# SCH_New-Project-123_2026-03-22.net
KiCad netlist of a schematic drawn in EasyEDA
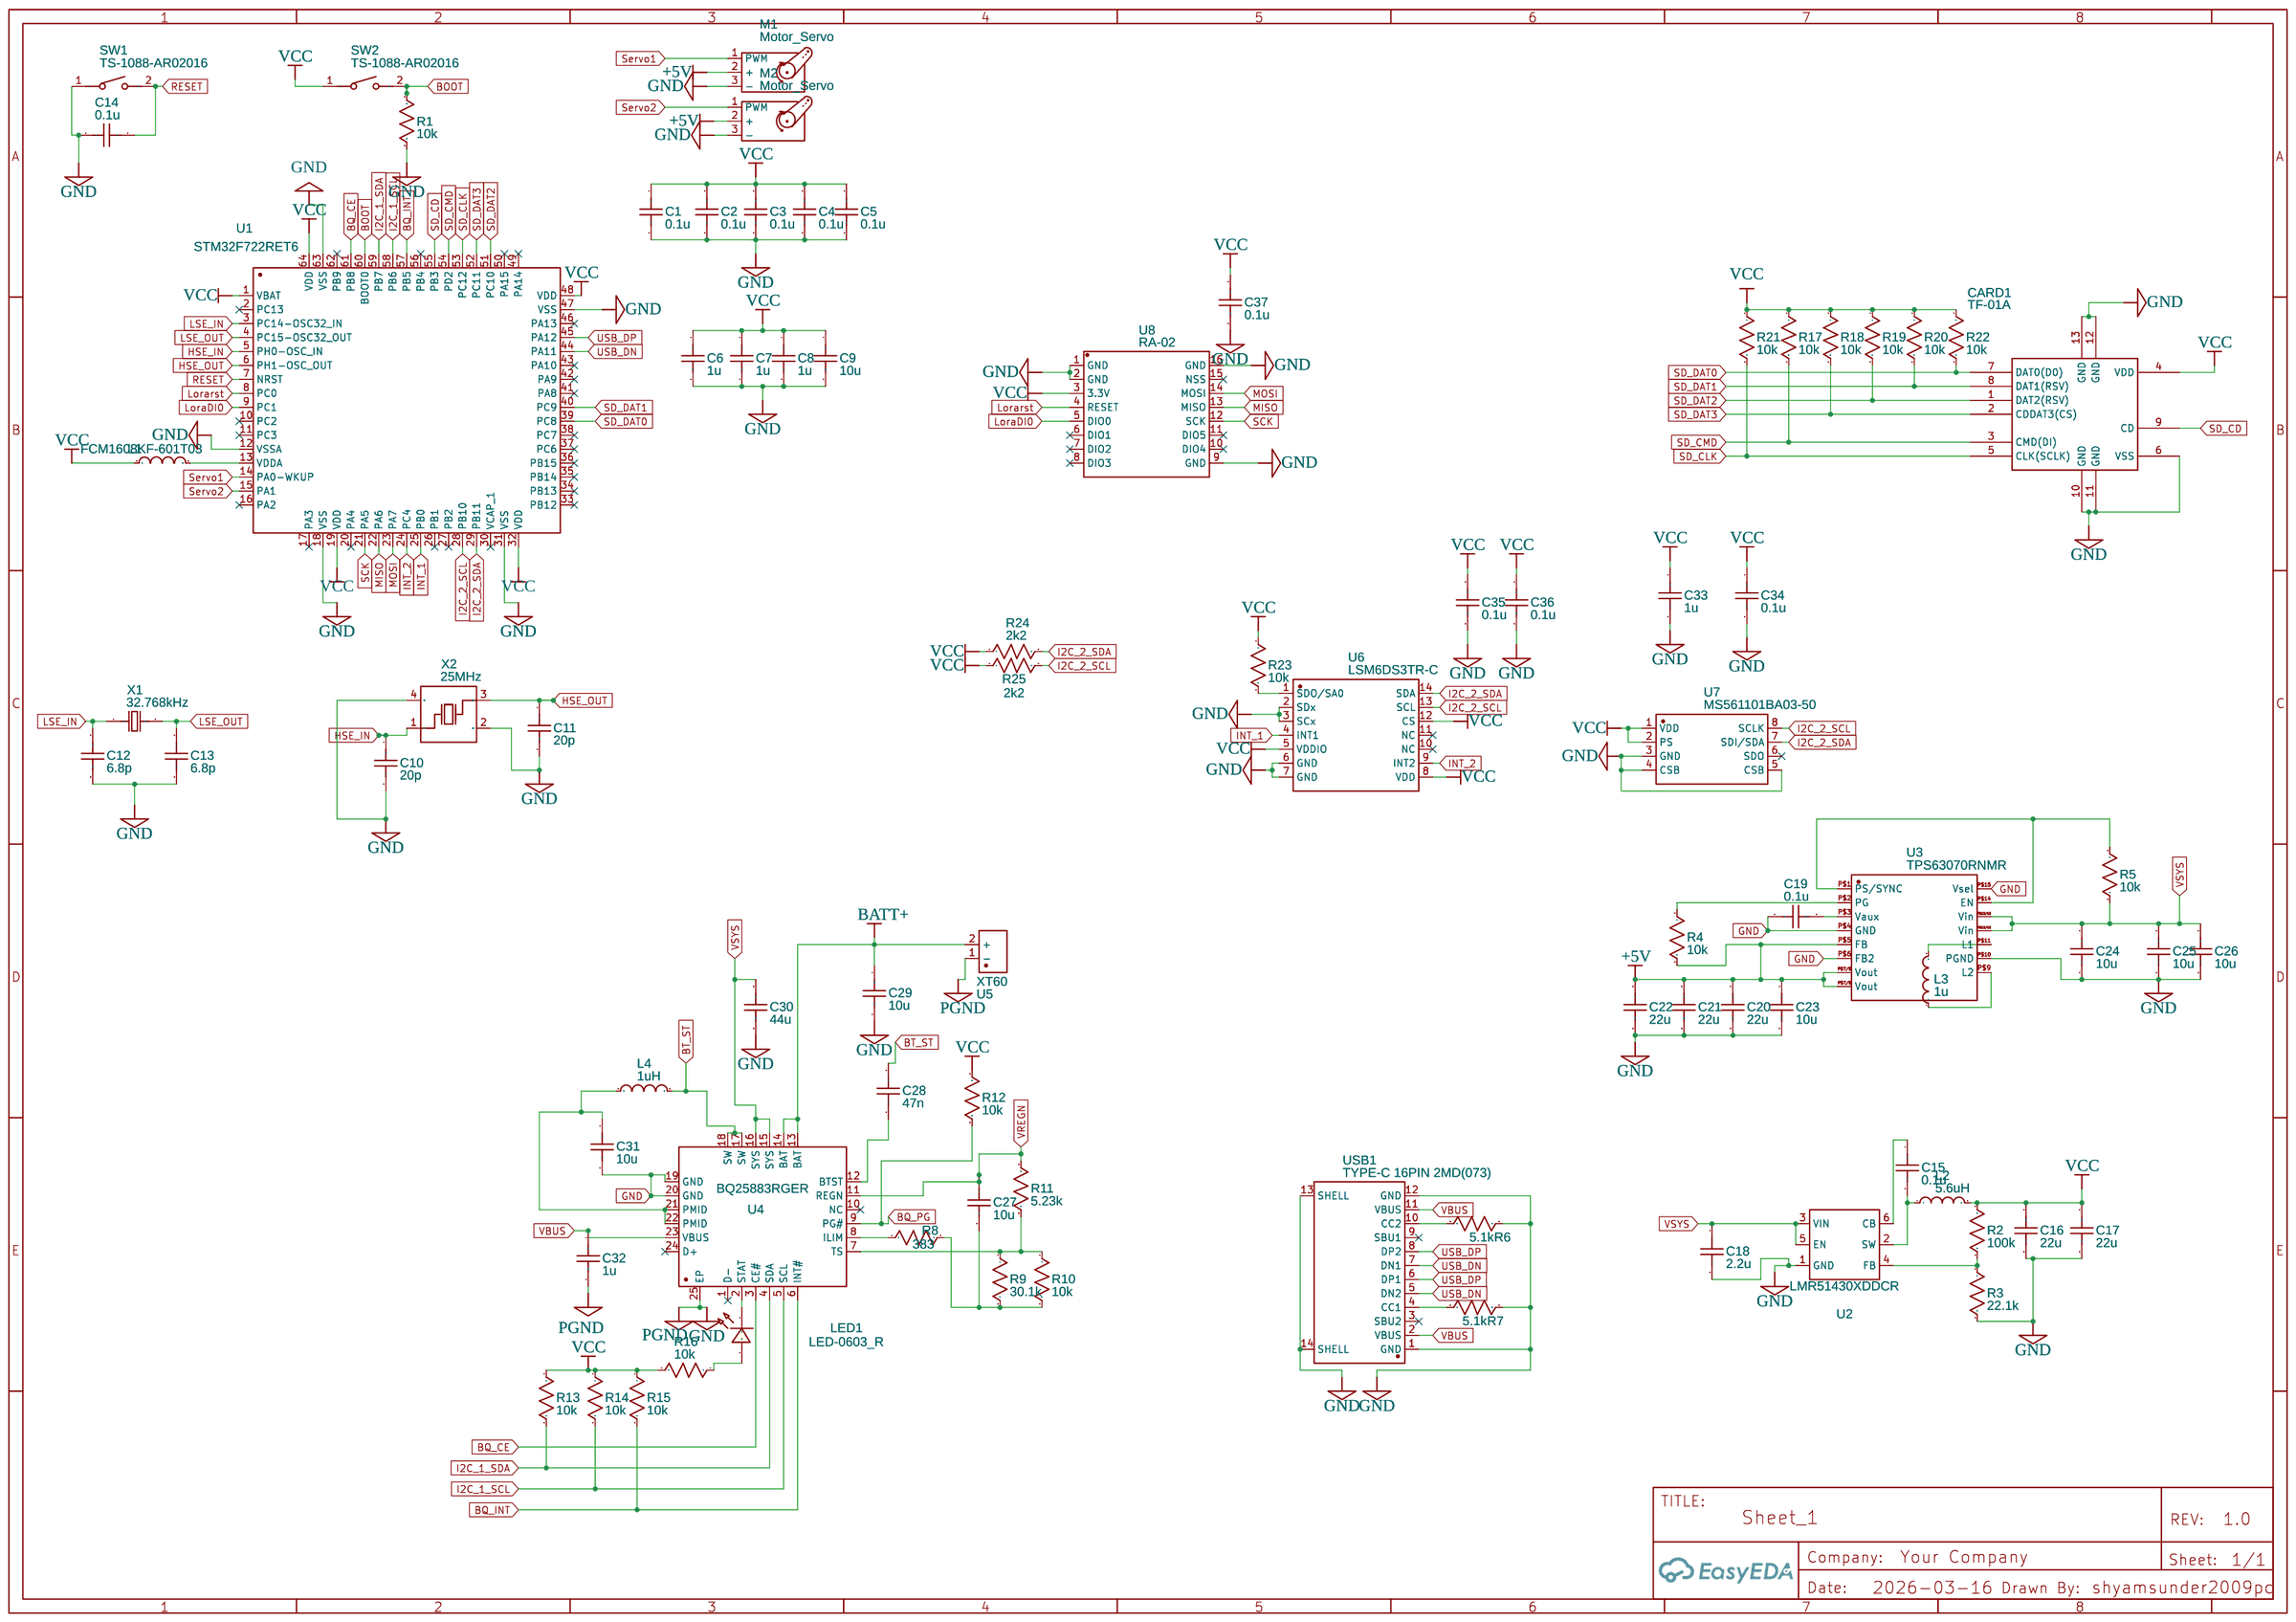
[diagram p0: schematic sheet]

(export (version "E")
  (design (tool "Eeschema 10.0.6"))
  (components
    (comp (ref "C1") (value "0.1u") (libsource (lib "") (part "C_0603_US")))
    (comp (ref "C2") (value "0.1u") (libsource (lib "") (part "C_0603_US")))
    (comp (ref "C3") (value "0.1u") (libsource (lib "") (part "C_0603_US")))
    (comp (ref "C4") (value "0.1u") (libsource (lib "") (part "C_0603_US")))
    (comp (ref "C5") (value "0.1u") (libsource (lib "") (part "C_0603_US")))
    (comp (ref "C6") (value "1u") (libsource (lib "") (part "C_0603_US")))
    (comp (ref "C7") (value "1u") (libsource (lib "") (part "C_0603_US")))
    (comp (ref "C8") (value "1u") (libsource (lib "") (part "C_0603_US")))
    (comp (ref "C9") (value "10u") (libsource (lib "") (part "C_0603_US")))
    (comp (ref "C10") (value "20p") (libsource (lib "") (part "C_0603_US")))
    (comp (ref "C11") (value "20p") (libsource (lib "") (part "C_0603_US")))
    (comp (ref "C12") (value "6.8p") (libsource (lib "") (part "C_0603_US")))
    (comp (ref "C13") (value "6.8p") (libsource (lib "") (part "C_0603_US")))
    (comp (ref "C14") (value "0.1u") (libsource (lib "") (part "C_0603_US_1")))
    (comp (ref "C15") (value "0.1u") (libsource (lib "") (part "C_0603_US")))
    (comp (ref "C16") (value "22u") (libsource (lib "") (part "C_0603_US")))
    (comp (ref "C17") (value "22u") (libsource (lib "") (part "C_0603_US")))
    (comp (ref "C18") (value "2.2u") (libsource (lib "") (part "C_0603_US")))
    (comp (ref "C19") (value "0.1u") (libsource (lib "") (part "C_0603_US_1")))
    (comp (ref "C20") (value "22u") (libsource (lib "") (part "C_0603_US")))
    (comp (ref "C21") (value "22u") (libsource (lib "") (part "C_0603_US")))
    (comp (ref "C22") (value "22u") (libsource (lib "") (part "C_0603_US")))
    (comp (ref "C23") (value "10u") (libsource (lib "") (part "C_0603_US")))
    (comp (ref "C24") (value "10u") (libsource (lib "") (part "C_0603_US")))
    (comp (ref "C25") (value "10u") (libsource (lib "") (part "C_0603_US")))
    (comp (ref "C26") (value "10u") (libsource (lib "") (part "C_0603_US")))
    (comp (ref "C27") (value "10u") (libsource (lib "") (part "C_0603_US")))
    (comp (ref "C28") (value "47n") (libsource (lib "") (part "C_0603_US_2")))
    (comp (ref "C29") (value "10u") (libsource (lib "") (part "C_0603_US")))
    (comp (ref "C30") (value "44u") (libsource (lib "") (part "C_0603_US")))
    (comp (ref "C31") (value "10u") (libsource (lib "") (part "C_0603_US")))
    (comp (ref "C32") (value "1u") (libsource (lib "") (part "C_0603_US")))
    (comp (ref "C33") (value "1u") (libsource (lib "") (part "C_0603_US")))
    (comp (ref "C34") (value "0.1u") (libsource (lib "") (part "C_0603_US")))
    (comp (ref "C35") (value "0.1u") (libsource (lib "") (part "C_0603_US")))
    (comp (ref "C36") (value "0.1u") (libsource (lib "") (part "C_0603_US")))
    (comp (ref "C37") (value "0.1u") (libsource (lib "") (part "C_0603_US")))
    (comp (ref "CARD1")
      (value "TF-01A")
      (fields (field (name "Manufacturer") "韩国韩荣"))
      (libsource (lib "") (part "TF-01A"))
    )
    (comp (ref "L1")
      (value "FCM1608KF-601T03")
      (fields (field (name "Manufacturer") "TAI-TECH(台庆)"))
      (libsource (lib "") (part "FCM1608KF-601T03"))
    )
    (comp (ref "L2")
      (value "5.6uH")
      (fields (field (name "Manufacturer Part") "YHNR3015-5R6M") (field (name "Manufacturer") "YJYCOIN(益嘉源)"))
      (libsource (lib "") (part "YHNR3015-5R6M"))
    )
    (comp (ref "L3") (value "1u") (libsource (lib "") (part "L0603_US")))
    (comp (ref "L4")
      (value "1uH")
      (fields
        (field (name "Manufacturer Part") "DFE252012F-1R0M=P2")
        (field (name "Manufacturer") "muRata(村田)")
      )
      (libsource (lib "") (part "DFE252012F-1R0M=P2"))
    )
    (comp (ref "LED1")
      (value "LED-0603_R")
      (fields
        (field (name "Manufacturer Part") "19-217/R6C-AL1M2VY/3T")
        (field (name "Manufacturer") "EVERLIGHT(台湾亿光)")
      )
      (libsource (lib "") (part "LED-0603_R"))
    )
    (comp (ref "M1") (value "Motor_Servo") (libsource (lib "") (part "Motor_Servo")))
    (comp (ref "M2") (value "Motor_Servo") (libsource (lib "") (part "Motor_Servo")))
    (comp (ref "R1") (value "10k") (libsource (lib "") (part "R_0603_US")))
    (comp (ref "R2") (value "100k") (libsource (lib "") (part "R_0603_US")))
    (comp (ref "R3") (value "22.1k") (libsource (lib "") (part "R_0603_US")))
    (comp (ref "R4") (value "10k") (libsource (lib "") (part "R_0603_US")))
    (comp (ref "R5") (value "10k") (libsource (lib "") (part "R_0603_US")))
    (comp (ref "R6") (value "5.1k") (libsource (lib "") (part "R_0603_US_1")))
    (comp (ref "R7") (value "5.1k") (libsource (lib "") (part "R_0603_US_1")))
    (comp (ref "R8") (value "383") (libsource (lib "") (part "R_0603_US_1")))
    (comp (ref "R9") (value "30.1k") (libsource (lib "") (part "R_0603_US")))
    (comp (ref "R10") (value "10k") (libsource (lib "") (part "R_0603_US")))
    (comp (ref "R11") (value "5.23k") (libsource (lib "") (part "R_0603_US")))
    (comp (ref "R12") (value "10k") (libsource (lib "") (part "R_0603_US")))
    (comp (ref "R13") (value "10k") (libsource (lib "") (part "R_0603_US")))
    (comp (ref "R14") (value "10k") (libsource (lib "") (part "R_0603_US")))
    (comp (ref "R15") (value "10k") (libsource (lib "") (part "R_0603_US")))
    (comp (ref "R16") (value "10k") (libsource (lib "") (part "R_0603_US_2")))
    (comp (ref "R17") (value "10k") (libsource (lib "") (part "R_0603_US")))
    (comp (ref "R18") (value "10k") (libsource (lib "") (part "R_0603_US")))
    (comp (ref "R19") (value "10k") (libsource (lib "") (part "R_0603_US")))
    (comp (ref "R20") (value "10k") (libsource (lib "") (part "R_0603_US")))
    (comp (ref "R21") (value "10k") (libsource (lib "") (part "R_0603_US")))
    (comp (ref "R22") (value "10k") (libsource (lib "") (part "R_0603_US")))
    (comp (ref "R23") (value "10k") (libsource (lib "") (part "R_0603_US")))
    (comp (ref "R24") (value "2k2") (libsource (lib "") (part "R_0603_US_1")))
    (comp (ref "R25") (value "2k2") (libsource (lib "") (part "R_0603_US_1")))
    (comp (ref "SW1")
      (value "TS-1088-AR02016")
      (fields (field (name "Manufacturer") "XUNPU(讯普)"))
      (libsource (lib "") (part "TS-1088-AR02016"))
    )
    (comp (ref "SW2")
      (value "TS-1088-AR02016")
      (fields (field (name "Manufacturer") "XUNPU(讯普)"))
      (libsource (lib "") (part "TS-1088-AR02016"))
    )
    (comp (ref "U1")
      (value "STM32F722RET6")
      (fields (field (name "Manufacturer") "ST(意法半导体)"))
      (libsource (lib "") (part "STM32F722RET6"))
    )
    (comp (ref "U2")
      (value "LMR51430XDDCR")
      (fields (field (name "Manufacturer") "TI(德州仪器)"))
      (libsource (lib "") (part "LMR51430XDDCR"))
    )
    (comp (ref "U3")
      (value "TPS63070RNMR")
      (fields (field (name "Manufacturer") "TI(德州仪器)"))
      (libsource (lib "") (part "TPS63070RNMR"))
    )
    (comp (ref "U4")
      (value "BQ25883RGER")
      (fields (field (name "Manufacturer") "TI(德州仪器)"))
      (libsource (lib "") (part "BQ25883RGER"))
    )
    (comp (ref "U5")
      (value "XT60")
      (fields (field (name "Manufacturer Part") "XT60-M.") (field (name "Manufacturer") "AMASS(艾迈斯)"))
      (libsource (lib "") (part "XT60"))
    )
    (comp (ref "U6")
      (value "LSM6DS3TR-C")
      (fields (field (name "Manufacturer") "ST(意法半导体)"))
      (libsource (lib "") (part "LSM6DS3TR-C"))
    )
    (comp (ref "U7")
      (value "MS561101BA03-50")
      (fields (field (name "Manufacturer") "TE Connectivity(泰科电子)"))
      (libsource (lib "") (part "MS561101BA03-50"))
    )
    (comp (ref "U8")
      (value "RA-02")
      (fields (field (name "Manufacturer Part") "Ra-02") (field (name "Manufacturer") "Ai-Thinker(安信可)"))
      (libsource (lib "") (part "RA-02"))
    )
    (comp (ref "USB1")
      (value "TYPE-C 16PIN 2MD(073)")
      (fields (field (name "Manufacturer") "SHOU HAN(首韩)"))
      (libsource (lib "") (part "TYPE-C 16PIN 2MD(073)"))
    )
    (comp (ref "X1")
      (value "32.768kHz")
      (fields (field (name "Manufacturer Part") "Q13FC13500004") (field (name "Manufacturer") "EPSON(爱普生)"))
      (libsource (lib "") (part "Q13FC1350000400"))
    )
    (comp (ref "X2")
      (value "25MHz")
      (fields (field (name "Manufacturer Part") "X322525MOB4SI") (field (name "Manufacturer") "YXC(扬兴晶振)"))
      (libsource (lib "") (part "X322525MOB4SI"))
    )
  )
  (nets
    (net (code "1") (name "+5V") (class "Default")
      (node (ref "C20") (pin "1") (pinfunction "1_1") (pintype "unspecified"))
      (node (ref "C21") (pin "1") (pinfunction "1_1") (pintype "unspecified"))
      (node (ref "C22") (pin "1") (pinfunction "1_1") (pintype "unspecified"))
      (node (ref "C23") (pin "1") (pinfunction "1_1") (pintype "unspecified"))
      (node (ref "M1") (pin "2") (pinfunction "+_2") (pintype "unspecified"))
      (node (ref "M2") (pin "2") (pinfunction "+_2") (pintype "unspecified"))
      (node (ref "R4") (pin "2") (pinfunction "2_2") (pintype "unspecified"))
      (node (ref "U3") (pin "P$5") (pinfunction "FB_P$5") (pintype "unspecified"))
      (node (ref "U3") (pin "P$7/8") (pinfunction "Vout_P$7/8") (pintype "unspecified"))
    )
    (net (code "2") (name "BATT+") (class "Default")
      (node (ref "C29") (pin "1") (pinfunction "1_1") (pintype "unspecified"))
      (node (ref "U4") (pin "13") (pinfunction "BAT_13") (pintype "unspecified"))
      (node (ref "U4") (pin "14") (pinfunction "BAT_14") (pintype "unspecified"))
      (node (ref "U5") (pin "2") (pinfunction "+_2") (pintype "unspecified"))
    )
    (net (code "3") (name "BOOT") (class "Default")
      (node (ref "R1") (pin "1") (pinfunction "1_1") (pintype "unspecified"))
      (node (ref "SW2") (pin "2") (pinfunction "2_2") (pintype "unspecified"))
      (node (ref "U1") (pin "60") (pinfunction "BOOT0_60") (pintype "unspecified"))
    )
    (net (code "4") (name "BQ_CE") (class "Default")
      (node (ref "U1") (pin "61") (pinfunction "PB8_61") (pintype "unspecified"))
      (node (ref "U4") (pin "3") (pinfunction "CE#_3") (pintype "unspecified"))
    )
    (net (code "5") (name "BQ_INT") (class "Default")
      (node (ref "R15") (pin "2") (pinfunction "2_2") (pintype "unspecified"))
      (node (ref "U1") (pin "57") (pinfunction "PB5_57") (pintype "unspecified"))
      (node (ref "U4") (pin "6") (pinfunction "INT#_6") (pintype "unspecified"))
    )
    (net (code "6") (name "BQ_PG") (class "Default")
      (node (ref "R12") (pin "2") (pinfunction "2_2") (pintype "unspecified"))
      (node (ref "U4") (pin "9") (pinfunction "PG#_9") (pintype "unspecified"))
    )
    (net (code "7") (name "BT_ST") (class "Default")
      (node (ref "C28") (pin "2") (pinfunction "2_2") (pintype "unspecified"))
      (node (ref "L4") (pin "2") (pinfunction "2_2") (pintype "unspecified"))
      (node (ref "U4") (pin "17") (pinfunction "SW_17") (pintype "unspecified"))
      (node (ref "U4") (pin "18") (pinfunction "SW_18") (pintype "unspecified"))
    )
    (net (code "8") (name "GND") (class "Default")
      (node (ref "C1") (pin "2") (pinfunction "2_2") (pintype "unspecified"))
      (node (ref "C10") (pin "2") (pinfunction "2_2") (pintype "unspecified"))
      (node (ref "C11") (pin "2") (pinfunction "2_2") (pintype "unspecified"))
      (node (ref "C12") (pin "2") (pinfunction "2_2") (pintype "unspecified"))
      (node (ref "C13") (pin "2") (pinfunction "2_2") (pintype "unspecified"))
      (node (ref "C14") (pin "1") (pinfunction "1_1") (pintype "unspecified"))
      (node (ref "C16") (pin "2") (pinfunction "2_2") (pintype "unspecified"))
      (node (ref "C17") (pin "2") (pinfunction "2_2") (pintype "unspecified"))
      (node (ref "C18") (pin "2") (pinfunction "2_2") (pintype "unspecified"))
      (node (ref "C19") (pin "1") (pinfunction "1_1") (pintype "unspecified"))
      (node (ref "C2") (pin "2") (pinfunction "2_2") (pintype "unspecified"))
      (node (ref "C20") (pin "2") (pinfunction "2_2") (pintype "unspecified"))
      (node (ref "C21") (pin "2") (pinfunction "2_2") (pintype "unspecified"))
      (node (ref "C22") (pin "2") (pinfunction "2_2") (pintype "unspecified"))
      (node (ref "C23") (pin "2") (pinfunction "2_2") (pintype "unspecified"))
      (node (ref "C24") (pin "2") (pinfunction "2_2") (pintype "unspecified"))
      (node (ref "C25") (pin "2") (pinfunction "2_2") (pintype "unspecified"))
      (node (ref "C26") (pin "2") (pinfunction "2_2") (pintype "unspecified"))
      (node (ref "C29") (pin "2") (pinfunction "2_2") (pintype "unspecified"))
      (node (ref "C3") (pin "2") (pinfunction "2_2") (pintype "unspecified"))
      (node (ref "C30") (pin "2") (pinfunction "2_2") (pintype "unspecified"))
      (node (ref "C31") (pin "2") (pinfunction "2_2") (pintype "unspecified"))
      (node (ref "C32") (pin "2") (pinfunction "2_2") (pintype "unspecified"))
      (node (ref "C33") (pin "2") (pinfunction "2_2") (pintype "unspecified"))
      (node (ref "C34") (pin "2") (pinfunction "2_2") (pintype "unspecified"))
      (node (ref "C35") (pin "2") (pinfunction "2_2") (pintype "unspecified"))
      (node (ref "C36") (pin "2") (pinfunction "2_2") (pintype "unspecified"))
      (node (ref "C37") (pin "2") (pinfunction "2_2") (pintype "unspecified"))
      (node (ref "C4") (pin "2") (pinfunction "2_2") (pintype "unspecified"))
      (node (ref "C5") (pin "2") (pinfunction "2_2") (pintype "unspecified"))
      (node (ref "C6") (pin "2") (pinfunction "2_2") (pintype "unspecified"))
      (node (ref "C7") (pin "2") (pinfunction "2_2") (pintype "unspecified"))
      (node (ref "C8") (pin "2") (pinfunction "2_2") (pintype "unspecified"))
      (node (ref "C9") (pin "2") (pinfunction "2_2") (pintype "unspecified"))
      (node (ref "CARD1") (pin "10") (pinfunction "GND_10") (pintype "input"))
      (node (ref "CARD1") (pin "11") (pinfunction "GND_11") (pintype "input"))
      (node (ref "CARD1") (pin "12") (pinfunction "GND_12") (pintype "input"))
      (node (ref "CARD1") (pin "13") (pinfunction "GND_13") (pintype "input"))
      (node (ref "CARD1") (pin "6") (pinfunction "VSS_6") (pintype "input"))
      (node (ref "M1") (pin "3") (pinfunction "-_3") (pintype "unspecified"))
      (node (ref "M2") (pin "3") (pinfunction "-_3") (pintype "unspecified"))
      (node (ref "R1") (pin "2") (pinfunction "2_2") (pintype "unspecified"))
      (node (ref "R3") (pin "2") (pinfunction "2_2") (pintype "unspecified"))
      (node (ref "R6") (pin "2") (pinfunction "2_2") (pintype "unspecified"))
      (node (ref "R7") (pin "2") (pinfunction "2_2") (pintype "unspecified"))
      (node (ref "SW1") (pin "1") (pinfunction "1_1") (pintype "unspecified"))
      (node (ref "U1") (pin "12") (pinfunction "VSSA_12") (pintype "unspecified"))
      (node (ref "U1") (pin "18") (pinfunction "VSS_18") (pintype "unspecified"))
      (node (ref "U1") (pin "31") (pinfunction "VSS_31") (pintype "unspecified"))
      (node (ref "U1") (pin "47") (pinfunction "VSS_47") (pintype "unspecified"))
      (node (ref "U1") (pin "63") (pinfunction "VSS_63") (pintype "unspecified"))
      (node (ref "U2") (pin "1") (pinfunction "GND_1") (pintype "unspecified"))
      (node (ref "U3") (pin "P$10") (pinfunction "PGND_P$10") (pintype "unspecified"))
      (node (ref "U3") (pin "P$15") (pinfunction "Vsel_P$15") (pintype "unspecified"))
      (node (ref "U3") (pin "P$4") (pinfunction "GND_P$4") (pintype "unspecified"))
      (node (ref "U3") (pin "P$6") (pinfunction "FB2_P$6") (pintype "unspecified"))
      (node (ref "U4") (pin "19") (pinfunction "GND_19") (pintype "unspecified"))
      (node (ref "U4") (pin "20") (pinfunction "GND_20") (pintype "unspecified"))
      (node (ref "U4") (pin "25") (pinfunction "EP_25") (pintype "unspecified"))
      (node (ref "U5") (pin "1") (pinfunction "-_1") (pintype "unspecified"))
      (node (ref "U6") (pin "2") (pinfunction "SDx_2") (pintype "unspecified"))
      (node (ref "U6") (pin "3") (pinfunction "SCx_3") (pintype "unspecified"))
      (node (ref "U6") (pin "6") (pinfunction "GND_6") (pintype "unspecified"))
      (node (ref "U6") (pin "7") (pinfunction "GND_7") (pintype "unspecified"))
      (node (ref "U7") (pin "3") (pinfunction "GND_3") (pintype "unspecified"))
      (node (ref "U7") (pin "4") (pinfunction "CSB_4") (pintype "unspecified"))
      (node (ref "U7") (pin "5") (pinfunction "CSB_5") (pintype "unspecified"))
      (node (ref "U8") (pin "1") (pinfunction "GND_1") (pintype "unspecified"))
      (node (ref "U8") (pin "16") (pinfunction "GND_16") (pintype "unspecified"))
      (node (ref "U8") (pin "2") (pinfunction "GND_2") (pintype "unspecified"))
      (node (ref "U8") (pin "9") (pinfunction "GND_9") (pintype "unspecified"))
      (node (ref "USB1") (pin "1") (pinfunction "GND_1") (pintype "unspecified"))
      (node (ref "USB1") (pin "12") (pinfunction "GND_12") (pintype "unspecified"))
      (node (ref "USB1") (pin "13") (pinfunction "SHELL_13") (pintype "unspecified"))
      (node (ref "USB1") (pin "14") (pinfunction "SHELL_14") (pintype "unspecified"))
      (node (ref "X2") (pin "2") (pinfunction "GND_2") (pintype "unspecified"))
      (node (ref "X2") (pin "4") (pinfunction "GND_4") (pintype "unspecified"))
    )
    (net (code "9") (name "HSE_IN") (class "Default")
      (node (ref "C10") (pin "1") (pinfunction "1_1") (pintype "unspecified"))
      (node (ref "U1") (pin "5") (pinfunction "PH0-OSC_IN_5") (pintype "unspecified"))
      (node (ref "X2") (pin "1") (pinfunction "OSC1_1") (pintype "unspecified"))
    )
    (net (code "10") (name "HSE_OUT") (class "Default")
      (node (ref "C11") (pin "1") (pinfunction "1_1") (pintype "unspecified"))
      (node (ref "U1") (pin "6") (pinfunction "PH1-OSC_OUT_6") (pintype "unspecified"))
      (node (ref "X2") (pin "3") (pinfunction "OSC2_3") (pintype "unspecified"))
    )
    (net (code "11") (name "I2C_1_SCL") (class "Default")
      (node (ref "R14") (pin "2") (pinfunction "2_2") (pintype "unspecified"))
      (node (ref "U1") (pin "58") (pinfunction "PB6_58") (pintype "unspecified"))
      (node (ref "U4") (pin "5") (pinfunction "SCL_5") (pintype "unspecified"))
    )
    (net (code "12") (name "I2C_1_SDA") (class "Default")
      (node (ref "R13") (pin "2") (pinfunction "2_2") (pintype "unspecified"))
      (node (ref "U1") (pin "59") (pinfunction "PB7_59") (pintype "unspecified"))
      (node (ref "U4") (pin "4") (pinfunction "SDA_4") (pintype "unspecified"))
    )
    (net (code "13") (name "I2C_2_SCL") (class "Default")
      (node (ref "R25") (pin "2") (pinfunction "2_2") (pintype "unspecified"))
      (node (ref "U1") (pin "28") (pinfunction "PB10_28") (pintype "unspecified"))
      (node (ref "U6") (pin "13") (pinfunction "SCL_13") (pintype "unspecified"))
      (node (ref "U7") (pin "8") (pinfunction "SCLK_8") (pintype "unspecified"))
    )
    (net (code "14") (name "I2C_2_SDA") (class "Default")
      (node (ref "R24") (pin "2") (pinfunction "2_2") (pintype "unspecified"))
      (node (ref "U1") (pin "29") (pinfunction "PB11_29") (pintype "unspecified"))
      (node (ref "U6") (pin "14") (pinfunction "SDA_14") (pintype "unspecified"))
      (node (ref "U7") (pin "7") (pinfunction "SDI/SDA_7") (pintype "unspecified"))
    )
    (net (code "15") (name "INT_1") (class "Default")
      (node (ref "U1") (pin "25") (pinfunction "PB0_25") (pintype "unspecified"))
      (node (ref "U6") (pin "4") (pinfunction "INT1_4") (pintype "unspecified"))
    )
    (net (code "16") (name "INT_2") (class "Default")
      (node (ref "U1") (pin "24") (pinfunction "PC4_24") (pintype "unspecified"))
      (node (ref "U6") (pin "9") (pinfunction "INT2_9") (pintype "unspecified"))
    )
    (net (code "17") (name "LSE_IN") (class "Default")
      (node (ref "C12") (pin "1") (pinfunction "1_1") (pintype "unspecified"))
      (node (ref "U1") (pin "3") (pinfunction "PC14-OSC32_IN_3") (pintype "unspecified"))
      (node (ref "X1") (pin "1") (pinfunction "1_1") (pintype "unspecified"))
    )
    (net (code "18") (name "LSE_OUT") (class "Default")
      (node (ref "C13") (pin "1") (pinfunction "1_1") (pintype "unspecified"))
      (node (ref "U1") (pin "4") (pinfunction "PC15-OSC32_OUT_4") (pintype "unspecified"))
      (node (ref "X1") (pin "2") (pinfunction "2_2") (pintype "unspecified"))
    )
    (net (code "19") (name "LoraDI0") (class "Default")
      (node (ref "U1") (pin "9") (pinfunction "PC1_9") (pintype "unspecified"))
      (node (ref "U8") (pin "5") (pinfunction "DIO0_5") (pintype "unspecified"))
    )
    (net (code "20") (name "Lorarst") (class "Default")
      (node (ref "U1") (pin "8") (pinfunction "PC0_8") (pintype "unspecified"))
      (node (ref "U8") (pin "4") (pinfunction "RESET_4") (pintype "unspecified"))
    )
    (net (code "21") (name "MISO") (class "Default")
      (node (ref "U1") (pin "22") (pinfunction "PA6_22") (pintype "unspecified"))
      (node (ref "U8") (pin "13") (pinfunction "MISO_13") (pintype "unspecified"))
    )
    (net (code "22") (name "MOSI") (class "Default")
      (node (ref "U1") (pin "23") (pinfunction "PA7_23") (pintype "unspecified"))
      (node (ref "U8") (pin "14") (pinfunction "MOSI_14") (pintype "unspecified"))
    )
    (net (code "23") (name "Net-(C27-Pad2)") (class "Default")
      (node (ref "C27") (pin "2") (pinfunction "2_2") (pintype "unspecified"))
      (node (ref "R10") (pin "2") (pinfunction "2_2") (pintype "unspecified"))
      (node (ref "R8") (pin "2") (pinfunction "2_2") (pintype "unspecified"))
      (node (ref "R9") (pin "2") (pinfunction "2_2") (pintype "unspecified"))
    )
    (net (code "24") (name "Net-(C31-Pad1)") (class "Default")
      (node (ref "C31") (pin "1") (pinfunction "1_1") (pintype "unspecified"))
      (node (ref "L4") (pin "1") (pinfunction "1_1") (pintype "unspecified"))
      (node (ref "U4") (pin "21") (pinfunction "PMID_21") (pintype "unspecified"))
      (node (ref "U4") (pin "22") (pinfunction "PMID_22") (pintype "unspecified"))
    )
    (net (code "25") (name "Net-(LED1-Pad1)") (class "Default")
      (node (ref "LED1") (pin "1") (pinfunction "1_1") (pintype "unspecified"))
      (node (ref "R16") (pin "1") (pinfunction "1_1") (pintype "unspecified"))
    )
    (net (code "26") (name "Net-(U1-VDDA)") (class "Default")
      (node (ref "L1") (pin "2") (pinfunction "2_2") (pintype "unspecified"))
      (node (ref "U1") (pin "13") (pinfunction "VDDA_13") (pintype "unspecified"))
    )
    (net (code "27") (name "Net-(U2-CB)") (class "Default")
      (node (ref "C15") (pin "1") (pinfunction "1_1") (pintype "unspecified"))
      (node (ref "U2") (pin "6") (pinfunction "CB_6") (pintype "unspecified"))
    )
    (net (code "28") (name "Net-(U2-FB)") (class "Default")
      (node (ref "R2") (pin "2") (pinfunction "2_2") (pintype "unspecified"))
      (node (ref "R3") (pin "1") (pinfunction "1_1") (pintype "unspecified"))
      (node (ref "U2") (pin "4") (pinfunction "FB_4") (pintype "unspecified"))
    )
    (net (code "29") (name "Net-(U2-SW)") (class "Default")
      (node (ref "C15") (pin "2") (pinfunction "2_2") (pintype "unspecified"))
      (node (ref "L2") (pin "1") (pinfunction "1_1") (pintype "unspecified"))
      (node (ref "U2") (pin "2") (pinfunction "SW_2") (pintype "unspecified"))
    )
    (net (code "30") (name "Net-(U3-EN)") (class "Default")
      (node (ref "R5") (pin "1") (pinfunction "1_1") (pintype "unspecified"))
      (node (ref "U3") (pin "P$1") (pinfunction "PS/SYNC_P$1") (pintype "unspecified"))
      (node (ref "U3") (pin "P$14") (pinfunction "EN_P$14") (pintype "unspecified"))
    )
    (net (code "31") (name "Net-(U3-L1)") (class "Default")
      (node (ref "L3") (pin "2") (pinfunction "2_2") (pintype "unspecified"))
      (node (ref "U3") (pin "P$11") (pinfunction "L1_P$11") (pintype "unspecified"))
    )
    (net (code "32") (name "Net-(U3-L2)") (class "Default")
      (node (ref "L3") (pin "1") (pinfunction "1_1") (pintype "unspecified"))
      (node (ref "U3") (pin "P$9") (pinfunction "L2_P$9") (pintype "unspecified"))
    )
    (net (code "33") (name "Net-(U3-PG)") (class "Default")
      (node (ref "R4") (pin "1") (pinfunction "1_1") (pintype "unspecified"))
      (node (ref "U3") (pin "P$2") (pinfunction "PG_P$2") (pintype "unspecified"))
    )
    (net (code "34") (name "Net-(U3-Vaux)") (class "Default")
      (node (ref "C19") (pin "2") (pinfunction "2_2") (pintype "unspecified"))
      (node (ref "U3") (pin "P$3") (pinfunction "Vaux_P$3") (pintype "unspecified"))
    )
    (net (code "35") (name "Net-(U4-BTST)") (class "Default")
      (node (ref "C28") (pin "1") (pinfunction "1_1") (pintype "unspecified"))
      (node (ref "U4") (pin "12") (pinfunction "BTST_12") (pintype "unspecified"))
    )
    (net (code "36") (name "Net-(U4-ILIM)") (class "Default")
      (node (ref "R8") (pin "1") (pinfunction "1_1") (pintype "unspecified"))
      (node (ref "U4") (pin "8") (pinfunction "ILIM_8") (pintype "unspecified"))
    )
    (net (code "37") (name "Net-(U4-STAT)") (class "Default")
      (node (ref "LED1") (pin "2") (pinfunction "2_2") (pintype "unspecified"))
      (node (ref "U4") (pin "2") (pinfunction "STAT_2") (pintype "unspecified"))
    )
    (net (code "38") (name "Net-(U4-TS)") (class "Default")
      (node (ref "R10") (pin "1") (pinfunction "1_1") (pintype "unspecified"))
      (node (ref "R11") (pin "2") (pinfunction "2_2") (pintype "unspecified"))
      (node (ref "R9") (pin "1") (pinfunction "1_1") (pintype "unspecified"))
      (node (ref "U4") (pin "7") (pinfunction "TS_7") (pintype "unspecified"))
    )
    (net (code "39") (name "Net-(U6-SDO{slash}SA0)") (class "Default")
      (node (ref "R23") (pin "2") (pinfunction "2_2") (pintype "unspecified"))
      (node (ref "U6") (pin "1") (pinfunction "SDO/SA0_1") (pintype "unspecified"))
    )
    (net (code "40") (name "Net-(USB1-CC1)") (class "Default")
      (node (ref "R7") (pin "1") (pinfunction "1_1") (pintype "unspecified"))
      (node (ref "USB1") (pin "4") (pinfunction "CC1_4") (pintype "unspecified"))
    )
    (net (code "41") (name "Net-(USB1-CC2)") (class "Default")
      (node (ref "R6") (pin "1") (pinfunction "1_1") (pintype "unspecified"))
      (node (ref "USB1") (pin "10") (pinfunction "CC2_10") (pintype "unspecified"))
    )
    (net (code "42") (name "RESET") (class "Default")
      (node (ref "C14") (pin "2") (pinfunction "2_2") (pintype "unspecified"))
      (node (ref "SW1") (pin "2") (pinfunction "2_2") (pintype "unspecified"))
      (node (ref "U1") (pin "7") (pinfunction "NRST_7") (pintype "unspecified"))
    )
    (net (code "43") (name "SCK") (class "Default")
      (node (ref "U1") (pin "21") (pinfunction "PA5_21") (pintype "unspecified"))
      (node (ref "U8") (pin "12") (pinfunction "SCK_12") (pintype "unspecified"))
    )
    (net (code "44") (name "SD_CD") (class "Default")
      (node (ref "CARD1") (pin "9") (pinfunction "CD_9") (pintype "input"))
      (node (ref "U1") (pin "55") (pinfunction "PB3_55") (pintype "unspecified"))
    )
    (net (code "45") (name "SD_CLK") (class "Default")
      (node (ref "CARD1") (pin "5") (pinfunction "CLK(SCLK)_5") (pintype "input"))
      (node (ref "R21") (pin "2") (pinfunction "2_2") (pintype "unspecified"))
      (node (ref "U1") (pin "53") (pinfunction "PC12_53") (pintype "unspecified"))
    )
    (net (code "46") (name "SD_CMD") (class "Default")
      (node (ref "CARD1") (pin "3") (pinfunction "CMD(DI)_3") (pintype "input"))
      (node (ref "R17") (pin "2") (pinfunction "2_2") (pintype "unspecified"))
      (node (ref "U1") (pin "54") (pinfunction "PD2_54") (pintype "unspecified"))
    )
    (net (code "47") (name "SD_DAT0") (class "Default")
      (node (ref "CARD1") (pin "7") (pinfunction "DAT0(D0)_7") (pintype "bidirectional"))
      (node (ref "R22") (pin "2") (pinfunction "2_2") (pintype "unspecified"))
      (node (ref "U1") (pin "39") (pinfunction "PC8_39") (pintype "unspecified"))
    )
    (net (code "48") (name "SD_DAT1") (class "Default")
      (node (ref "CARD1") (pin "8") (pinfunction "DAT1(RSV)_8") (pintype "bidirectional"))
      (node (ref "R20") (pin "2") (pinfunction "2_2") (pintype "unspecified"))
      (node (ref "U1") (pin "40") (pinfunction "PC9_40") (pintype "unspecified"))
    )
    (net (code "49") (name "SD_DAT2") (class "Default")
      (node (ref "CARD1") (pin "1") (pinfunction "DAT2(RSV)_1") (pintype "bidirectional"))
      (node (ref "R19") (pin "2") (pinfunction "2_2") (pintype "unspecified"))
      (node (ref "U1") (pin "51") (pinfunction "PC10_51") (pintype "unspecified"))
    )
    (net (code "50") (name "SD_DAT3") (class "Default")
      (node (ref "CARD1") (pin "2") (pinfunction "CDDAT3(CS)_2") (pintype "bidirectional"))
      (node (ref "R18") (pin "2") (pinfunction "2_2") (pintype "unspecified"))
      (node (ref "U1") (pin "52") (pinfunction "PC11_52") (pintype "unspecified"))
    )
    (net (code "51") (name "Servo1") (class "Default")
      (node (ref "M1") (pin "1") (pinfunction "PWM_1") (pintype "unspecified"))
      (node (ref "U1") (pin "14") (pinfunction "PA0-WKUP_14") (pintype "unspecified"))
    )
    (net (code "52") (name "Servo2") (class "Default")
      (node (ref "M2") (pin "1") (pinfunction "PWM_1") (pintype "unspecified"))
      (node (ref "U1") (pin "15") (pinfunction "PA1_15") (pintype "unspecified"))
    )
    (net (code "53") (name "USB_DN") (class "Default")
      (node (ref "U1") (pin "44") (pinfunction "PA11_44") (pintype "unspecified"))
      (node (ref "USB1") (pin "5") (pinfunction "DN2_5") (pintype "unspecified"))
      (node (ref "USB1") (pin "7") (pinfunction "DN1_7") (pintype "unspecified"))
    )
    (net (code "54") (name "USB_DP") (class "Default")
      (node (ref "U1") (pin "45") (pinfunction "PA12_45") (pintype "unspecified"))
      (node (ref "USB1") (pin "6") (pinfunction "DP1_6") (pintype "unspecified"))
      (node (ref "USB1") (pin "8") (pinfunction "DP2_8") (pintype "unspecified"))
    )
    (net (code "55") (name "VBUS") (class "Default")
      (node (ref "C32") (pin "1") (pinfunction "1_1") (pintype "unspecified"))
      (node (ref "U4") (pin "23") (pinfunction "VBUS_23") (pintype "unspecified"))
      (node (ref "USB1") (pin "11") (pinfunction "VBUS_11") (pintype "unspecified"))
      (node (ref "USB1") (pin "2") (pinfunction "VBUS_2") (pintype "unspecified"))
    )
    (net (code "56") (name "VCC") (class "Default")
      (node (ref "C1") (pin "1") (pinfunction "1_1") (pintype "unspecified"))
      (node (ref "C16") (pin "1") (pinfunction "1_1") (pintype "unspecified"))
      (node (ref "C17") (pin "1") (pinfunction "1_1") (pintype "unspecified"))
      (node (ref "C2") (pin "1") (pinfunction "1_1") (pintype "unspecified"))
      (node (ref "C3") (pin "1") (pinfunction "1_1") (pintype "unspecified"))
      (node (ref "C33") (pin "1") (pinfunction "1_1") (pintype "unspecified"))
      (node (ref "C34") (pin "1") (pinfunction "1_1") (pintype "unspecified"))
      (node (ref "C35") (pin "1") (pinfunction "1_1") (pintype "unspecified"))
      (node (ref "C36") (pin "1") (pinfunction "1_1") (pintype "unspecified"))
      (node (ref "C37") (pin "1") (pinfunction "1_1") (pintype "unspecified"))
      (node (ref "C4") (pin "1") (pinfunction "1_1") (pintype "unspecified"))
      (node (ref "C5") (pin "1") (pinfunction "1_1") (pintype "unspecified"))
      (node (ref "C6") (pin "1") (pinfunction "1_1") (pintype "unspecified"))
      (node (ref "C7") (pin "1") (pinfunction "1_1") (pintype "unspecified"))
      (node (ref "C8") (pin "1") (pinfunction "1_1") (pintype "unspecified"))
      (node (ref "C9") (pin "1") (pinfunction "1_1") (pintype "unspecified"))
      (node (ref "CARD1") (pin "4") (pinfunction "VDD_4") (pintype "input"))
      (node (ref "L1") (pin "1") (pinfunction "1_1") (pintype "unspecified"))
      (node (ref "L2") (pin "2") (pinfunction "2_2") (pintype "unspecified"))
      (node (ref "R12") (pin "1") (pinfunction "1_1") (pintype "unspecified"))
      (node (ref "R13") (pin "1") (pinfunction "1_1") (pintype "unspecified"))
      (node (ref "R14") (pin "1") (pinfunction "1_1") (pintype "unspecified"))
      (node (ref "R15") (pin "1") (pinfunction "1_1") (pintype "unspecified"))
      (node (ref "R16") (pin "2") (pinfunction "2_2") (pintype "unspecified"))
      (node (ref "R17") (pin "1") (pinfunction "1_1") (pintype "unspecified"))
      (node (ref "R18") (pin "1") (pinfunction "1_1") (pintype "unspecified"))
      (node (ref "R19") (pin "1") (pinfunction "1_1") (pintype "unspecified"))
      (node (ref "R2") (pin "1") (pinfunction "1_1") (pintype "unspecified"))
      (node (ref "R20") (pin "1") (pinfunction "1_1") (pintype "unspecified"))
      (node (ref "R21") (pin "1") (pinfunction "1_1") (pintype "unspecified"))
      (node (ref "R22") (pin "1") (pinfunction "1_1") (pintype "unspecified"))
      (node (ref "R23") (pin "1") (pinfunction "1_1") (pintype "unspecified"))
      (node (ref "R24") (pin "1") (pinfunction "1_1") (pintype "unspecified"))
      (node (ref "R25") (pin "1") (pinfunction "1_1") (pintype "unspecified"))
      (node (ref "SW2") (pin "1") (pinfunction "1_1") (pintype "unspecified"))
      (node (ref "U1") (pin "1") (pinfunction "VBAT_1") (pintype "unspecified"))
      (node (ref "U1") (pin "19") (pinfunction "VDD_19") (pintype "unspecified"))
      (node (ref "U1") (pin "32") (pinfunction "VDD_32") (pintype "unspecified"))
      (node (ref "U1") (pin "48") (pinfunction "VDD_48") (pintype "unspecified"))
      (node (ref "U1") (pin "64") (pinfunction "VDD_64") (pintype "unspecified"))
      (node (ref "U6") (pin "12") (pinfunction "CS_12") (pintype "unspecified"))
      (node (ref "U6") (pin "5") (pinfunction "VDDIO_5") (pintype "unspecified"))
      (node (ref "U6") (pin "8") (pinfunction "VDD_8") (pintype "unspecified"))
      (node (ref "U7") (pin "1") (pinfunction "VDD_1") (pintype "unspecified"))
      (node (ref "U7") (pin "2") (pinfunction "PS_2") (pintype "unspecified"))
      (node (ref "U8") (pin "3") (pinfunction "3.3V_3") (pintype "unspecified"))
    )
    (net (code "57") (name "VREGN") (class "Default")
      (node (ref "C27") (pin "1") (pinfunction "1_1") (pintype "unspecified"))
      (node (ref "R11") (pin "1") (pinfunction "1_1") (pintype "unspecified"))
      (node (ref "U4") (pin "11") (pinfunction "REGN_11") (pintype "unspecified"))
    )
    (net (code "58") (name "VSYS") (class "Default")
      (node (ref "C18") (pin "1") (pinfunction "1_1") (pintype "unspecified"))
      (node (ref "C24") (pin "1") (pinfunction "1_1") (pintype "unspecified"))
      (node (ref "C25") (pin "1") (pinfunction "1_1") (pintype "unspecified"))
      (node (ref "C26") (pin "1") (pinfunction "1_1") (pintype "unspecified"))
      (node (ref "C30") (pin "1") (pinfunction "1_1") (pintype "unspecified"))
      (node (ref "R5") (pin "2") (pinfunction "2_2") (pintype "unspecified"))
      (node (ref "U2") (pin "3") (pinfunction "VIN_3") (pintype "unspecified"))
      (node (ref "U2") (pin "5") (pinfunction "EN_5") (pintype "unspecified"))
      (node (ref "U3") (pin "P$12/13") (pinfunction "Vin_P$12/13") (pintype "unspecified"))
      (node (ref "U4") (pin "15") (pinfunction "SYS_15") (pintype "unspecified"))
      (node (ref "U4") (pin "16") (pinfunction "SYS_16") (pintype "unspecified"))
    )
    (net (code "59") (name "unconnected-(U1-PA2-Pad16)") (class "Default")
      (node (ref "U1") (pin "16") (pinfunction "PA2_16") (pintype "unspecified+no_connect"))
    )
    (net (code "60") (name "unconnected-(U1-PA3-Pad17)") (class "Default")
      (node (ref "U1") (pin "17") (pinfunction "PA3_17") (pintype "unspecified+no_connect"))
    )
    (net (code "61") (name "unconnected-(U1-PA4-Pad20)") (class "Default")
      (node (ref "U1") (pin "20") (pinfunction "PA4_20") (pintype "unspecified+no_connect"))
    )
    (net (code "62") (name "unconnected-(U1-PA8-Pad41)") (class "Default")
      (node (ref "U1") (pin "41") (pinfunction "PA8_41") (pintype "unspecified+no_connect"))
    )
    (net (code "63") (name "unconnected-(U1-PA9-Pad42)") (class "Default")
      (node (ref "U1") (pin "42") (pinfunction "PA9_42") (pintype "unspecified+no_connect"))
    )
    (net (code "64") (name "unconnected-(U1-PA10-Pad43)") (class "Default")
      (node (ref "U1") (pin "43") (pinfunction "PA10_43") (pintype "unspecified+no_connect"))
    )
    (net (code "65") (name "unconnected-(U1-PA13-Pad46)") (class "Default")
      (node (ref "U1") (pin "46") (pinfunction "PA13_46") (pintype "unspecified+no_connect"))
    )
    (net (code "66") (name "unconnected-(U1-PA14-Pad49)") (class "Default")
      (node (ref "U1") (pin "49") (pinfunction "PA14_49") (pintype "unspecified+no_connect"))
    )
    (net (code "67") (name "unconnected-(U1-PA15-Pad50)") (class "Default")
      (node (ref "U1") (pin "50") (pinfunction "PA15_50") (pintype "unspecified+no_connect"))
    )
    (net (code "68") (name "unconnected-(U1-PB1-Pad26)") (class "Default")
      (node (ref "U1") (pin "26") (pinfunction "PB1_26") (pintype "unspecified+no_connect"))
    )
    (net (code "69") (name "unconnected-(U1-PB2-Pad27)") (class "Default")
      (node (ref "U1") (pin "27") (pinfunction "PB2_27") (pintype "unspecified+no_connect"))
    )
    (net (code "70") (name "unconnected-(U1-PB4-Pad56)") (class "Default")
      (node (ref "U1") (pin "56") (pinfunction "PB4_56") (pintype "unspecified+no_connect"))
    )
    (net (code "71") (name "unconnected-(U1-PB9-Pad62)") (class "Default")
      (node (ref "U1") (pin "62") (pinfunction "PB9_62") (pintype "unspecified+no_connect"))
    )
    (net (code "72") (name "unconnected-(U1-PB12-Pad33)") (class "Default")
      (node (ref "U1") (pin "33") (pinfunction "PB12_33") (pintype "unspecified+no_connect"))
    )
    (net (code "73") (name "unconnected-(U1-PB13-Pad34)") (class "Default")
      (node (ref "U1") (pin "34") (pinfunction "PB13_34") (pintype "unspecified+no_connect"))
    )
    (net (code "74") (name "unconnected-(U1-PB14-Pad35)") (class "Default")
      (node (ref "U1") (pin "35") (pinfunction "PB14_35") (pintype "unspecified+no_connect"))
    )
    (net (code "75") (name "unconnected-(U1-PB15-Pad36)") (class "Default")
      (node (ref "U1") (pin "36") (pinfunction "PB15_36") (pintype "unspecified+no_connect"))
    )
    (net (code "76") (name "unconnected-(U1-PC2-Pad10)") (class "Default")
      (node (ref "U1") (pin "10") (pinfunction "PC2_10") (pintype "unspecified+no_connect"))
    )
    (net (code "77") (name "unconnected-(U1-PC3-Pad11)") (class "Default")
      (node (ref "U1") (pin "11") (pinfunction "PC3_11") (pintype "unspecified+no_connect"))
    )
    (net (code "78") (name "unconnected-(U1-PC6-Pad37)") (class "Default")
      (node (ref "U1") (pin "37") (pinfunction "PC6_37") (pintype "unspecified+no_connect"))
    )
    (net (code "79") (name "unconnected-(U1-PC7-Pad38)") (class "Default")
      (node (ref "U1") (pin "38") (pinfunction "PC7_38") (pintype "unspecified+no_connect"))
    )
    (net (code "80") (name "unconnected-(U1-PC13-Pad2)") (class "Default")
      (node (ref "U1") (pin "2") (pinfunction "PC13_2") (pintype "unspecified+no_connect"))
    )
    (net (code "81") (name "unconnected-(U1-VCAP_1-Pad30)") (class "Default")
      (node (ref "U1") (pin "30") (pinfunction "VCAP_1_30") (pintype "unspecified+no_connect"))
    )
    (net (code "82") (name "unconnected-(U4-D+-Pad24)") (class "Default")
      (node (ref "U4") (pin "24") (pinfunction "D+_24") (pintype "unspecified+no_connect"))
    )
    (net (code "83") (name "unconnected-(U4-D--Pad1)") (class "Default")
      (node (ref "U4") (pin "1") (pinfunction "D-_1") (pintype "unspecified+no_connect"))
    )
    (net (code "84") (name "unconnected-(U4-NC-Pad10)") (class "Default")
      (node (ref "U4") (pin "10") (pinfunction "NC_10") (pintype "unspecified+no_connect"))
    )
    (net (code "85") (name "unconnected-(U6-NC-Pad10)") (class "Default")
      (node (ref "U6") (pin "10") (pinfunction "NC_10") (pintype "unspecified+no_connect"))
    )
    (net (code "86") (name "unconnected-(U6-NC-Pad11)") (class "Default")
      (node (ref "U6") (pin "11") (pinfunction "NC_11") (pintype "unspecified+no_connect"))
    )
    (net (code "87") (name "unconnected-(U7-SDO-Pad6)") (class "Default")
      (node (ref "U7") (pin "6") (pinfunction "SDO_6") (pintype "unspecified+no_connect"))
    )
    (net (code "88") (name "unconnected-(U8-DIO1-Pad6)") (class "Default")
      (node (ref "U8") (pin "6") (pinfunction "DIO1_6") (pintype "unspecified+no_connect"))
    )
    (net (code "89") (name "unconnected-(U8-DIO2-Pad7)") (class "Default")
      (node (ref "U8") (pin "7") (pinfunction "DIO2_7") (pintype "unspecified+no_connect"))
    )
    (net (code "90") (name "unconnected-(U8-DIO3-Pad8)") (class "Default")
      (node (ref "U8") (pin "8") (pinfunction "DIO3_8") (pintype "unspecified+no_connect"))
    )
    (net (code "91") (name "unconnected-(U8-DIO4-Pad10)") (class "Default")
      (node (ref "U8") (pin "10") (pinfunction "DIO4_10") (pintype "unspecified+no_connect"))
    )
    (net (code "92") (name "unconnected-(U8-DIO5-Pad11)") (class "Default")
      (node (ref "U8") (pin "11") (pinfunction "DIO5_11") (pintype "unspecified+no_connect"))
    )
    (net (code "93") (name "unconnected-(U8-NSS-Pad15)") (class "Default")
      (node (ref "U8") (pin "15") (pinfunction "NSS_15") (pintype "unspecified+no_connect"))
    )
    (net (code "94") (name "unconnected-(USB1-SBU1-Pad9)") (class "Default")
      (node (ref "USB1") (pin "9") (pinfunction "SBU1_9") (pintype "unspecified+no_connect"))
    )
    (net (code "95") (name "unconnected-(USB1-SBU2-Pad3)") (class "Default")
      (node (ref "USB1") (pin "3") (pinfunction "SBU2_3") (pintype "unspecified+no_connect"))
    )
  )
)
